# SiLPA_HE_EEM_Connectors.net
KiCad netlist of a schematic drawn in Altium Designer
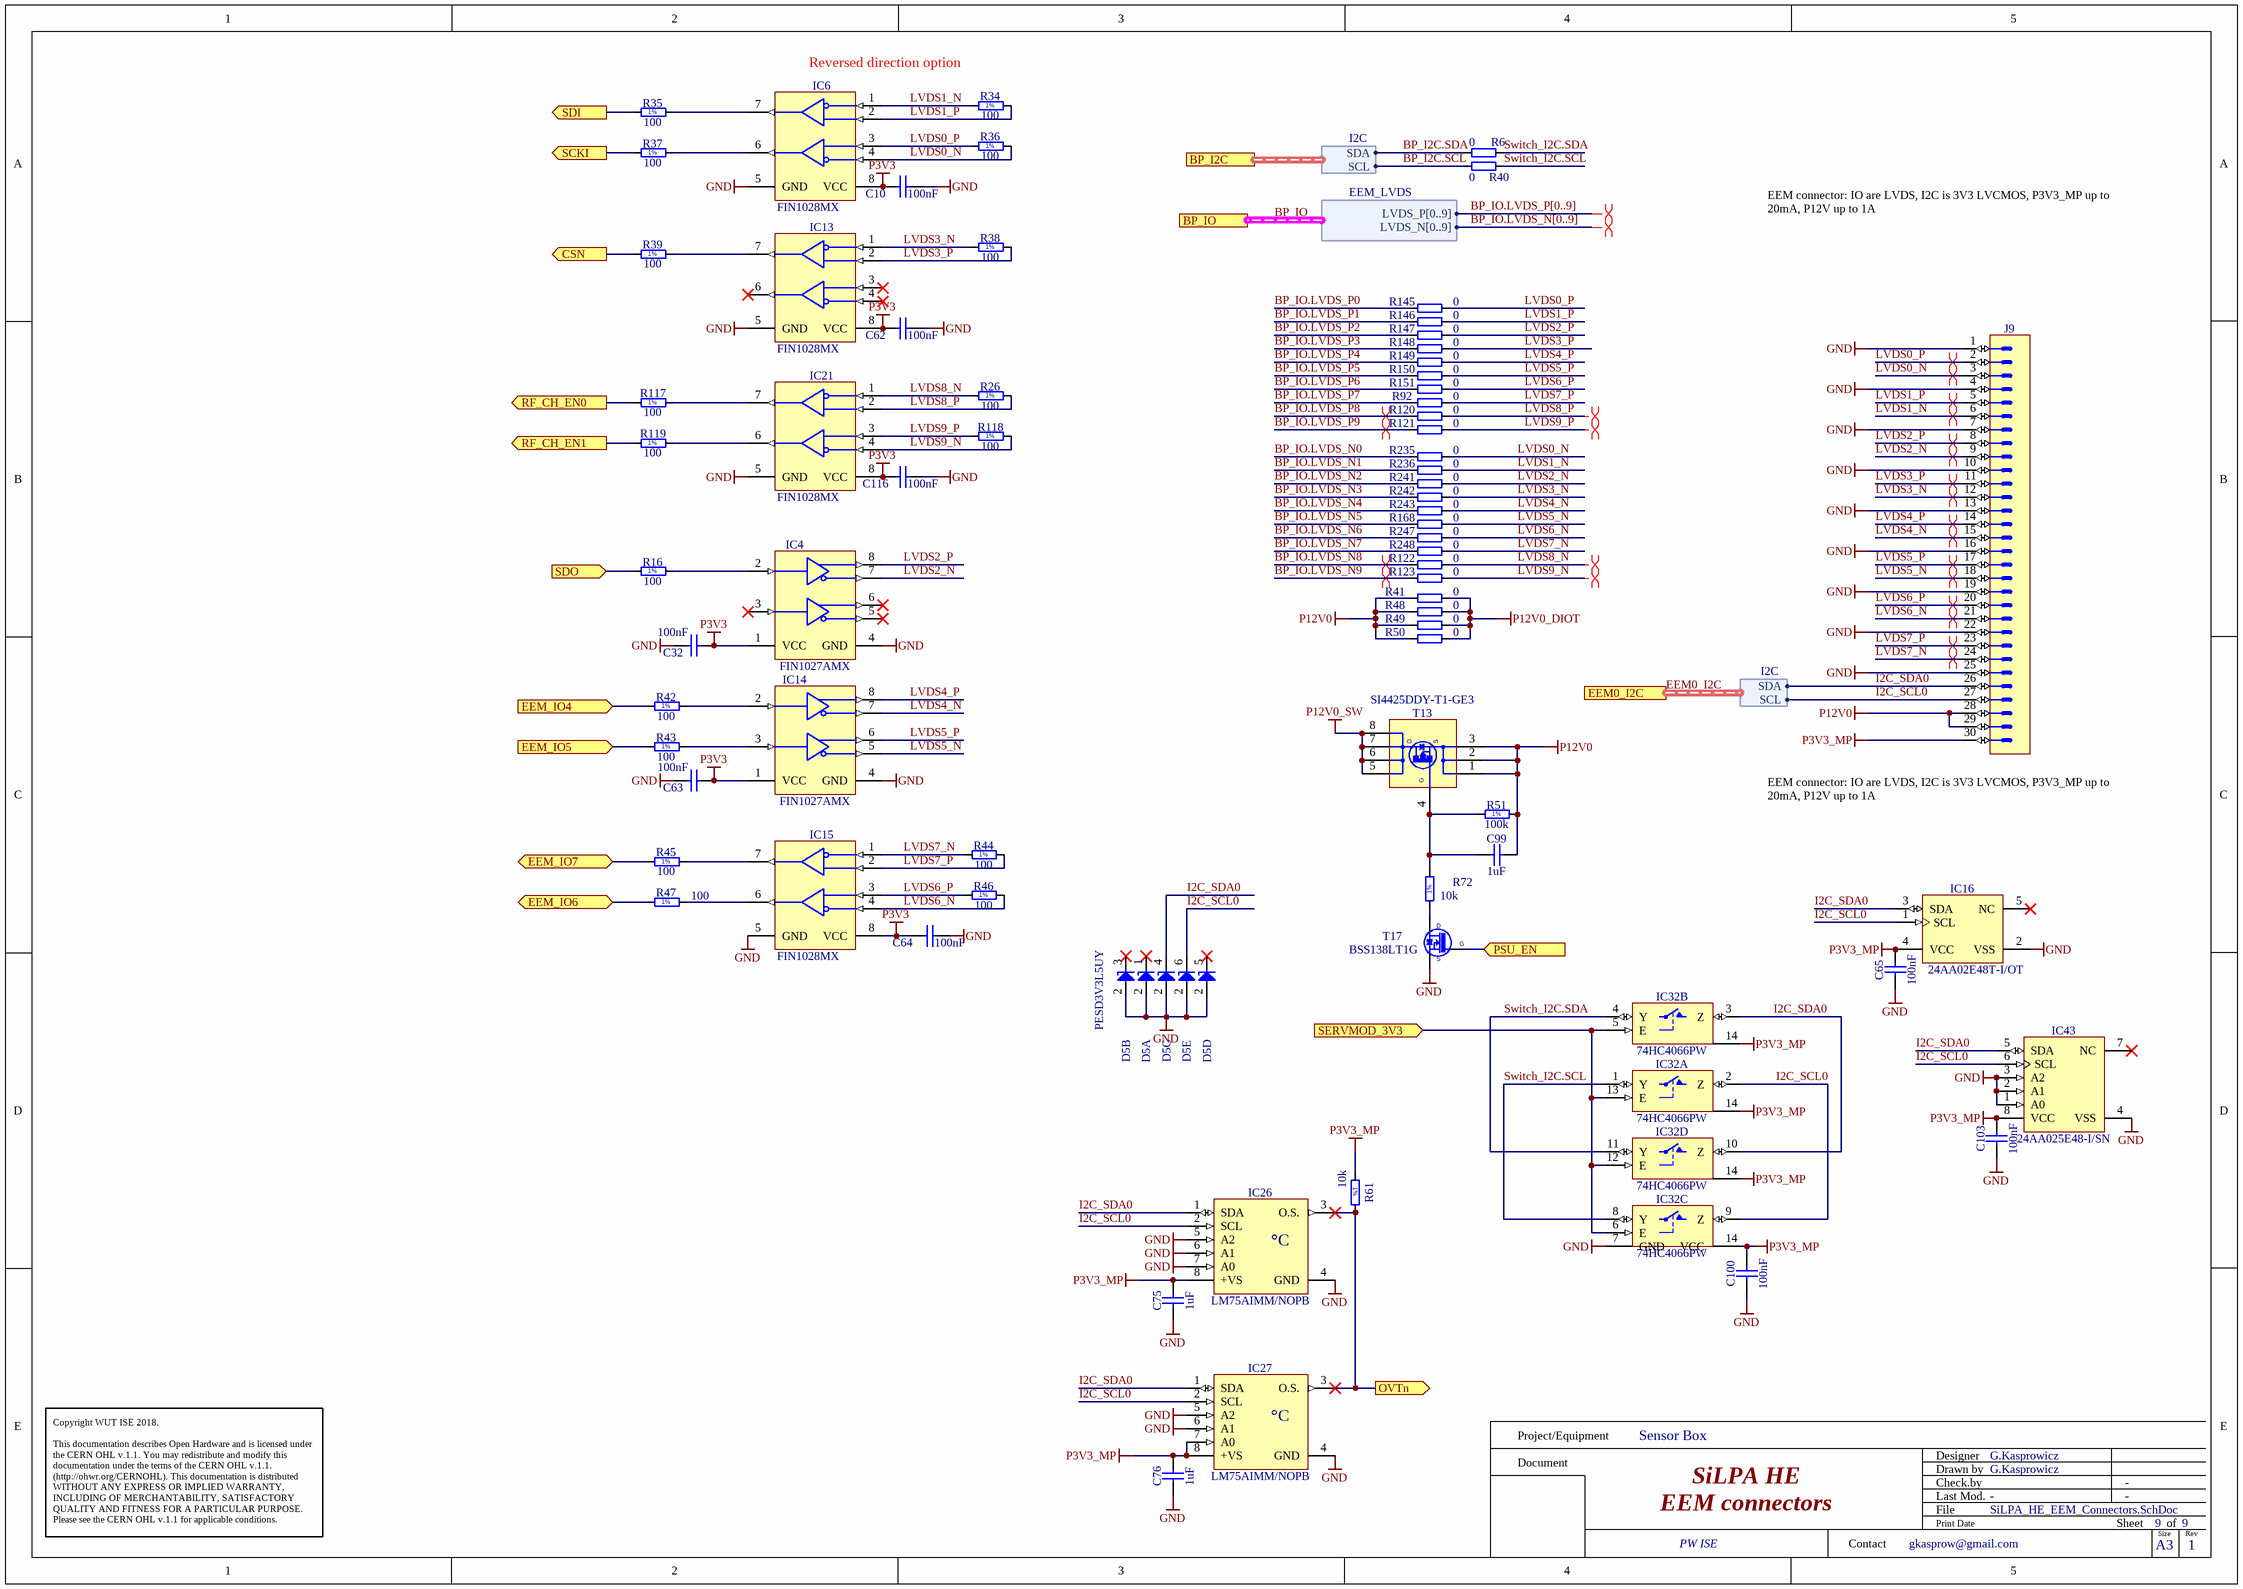
[diagram p0: SiLPA_HE_EEM_Connectors.SchDoc]

(export (version "E")
  (design (tool "Eeschema 10.0.6"))
  (components
    (comp (ref "C10")
      (value "100nF")
      (footprint "CAPC1005X55N")
      (description "Non-polarised capacitor")
      (fields
        (field (name "PART NUMBER") "CC0402_100NF_16V_10%_X5R")
        (field (name "VOLTAGE") "16V")
        (field (name "AUTHOR") "CERN DEM JLC")
      )
      (libsource (lib "Capacitors") (part "Capacitor - non polarized"))
    )
    (comp (ref "C32")
      (value "100nF")
      (footprint "CAPC1005X55N")
      (description "Non-polarised capacitor")
      (fields
        (field (name "PART NUMBER") "CC0402_100NF_16V_10%_X5R")
        (field (name "VOLTAGE") "16V")
        (field (name "AUTHOR") "CERN DEM JLC")
      )
      (libsource (lib "Capacitors") (part "Capacitor - non polarized"))
    )
    (comp (ref "C62")
      (value "100nF")
      (footprint "CAPC1005X55N")
      (description "Non-polarised capacitor")
      (fields
        (field (name "PART NUMBER") "CC0402_100NF_16V_10%_X5R")
        (field (name "VOLTAGE") "16V")
        (field (name "AUTHOR") "CERN DEM JLC")
      )
      (libsource (lib "Capacitors") (part "Capacitor - non polarized"))
    )
    (comp (ref "C63")
      (value "100nF")
      (footprint "CAPC1005X55N")
      (description "Non-polarised capacitor")
      (fields
        (field (name "PART NUMBER") "CC0402_100NF_16V_10%_X5R")
        (field (name "VOLTAGE") "16V")
        (field (name "AUTHOR") "CERN DEM JLC")
      )
      (libsource (lib "Capacitors") (part "Capacitor - non polarized"))
    )
    (comp (ref "C64")
      (value "100nF")
      (footprint "CAPC1005X55N")
      (description "Non-polarised capacitor")
      (fields
        (field (name "PART NUMBER") "CC0402_100NF_16V_10%_X5R")
        (field (name "VOLTAGE") "16V")
        (field (name "AUTHOR") "CERN DEM JLC")
      )
      (libsource (lib "Capacitors") (part "Capacitor - non polarized"))
    )
    (comp (ref "C65")
      (value "100nF")
      (footprint "CAPC1005X55N")
      (description "Non-polarised capacitor")
      (fields
        (field (name "PART NUMBER") "CC0402_100NF_16V_10%_X5R")
        (field (name "VOLTAGE") "16V")
        (field (name "AUTHOR") "CERN DEM JLC")
      )
      (libsource (lib "Capacitors") (part "Capacitor - non polarized"))
    )
    (comp (ref "C75")
      (value "1uF")
      (footprint "CAPC1005X55N")
      (description "Non-polarised capacitor")
      (fields
        (field (name "PART NUMBER") "CC0402_1UF_16V_10%_X5R")
        (field (name "VOLTAGE") "16V")
        (field (name "AUTHOR") "CERN DEM JLC")
      )
      (libsource (lib "Capacitors") (part "Capacitor - non polarized"))
    )
    (comp (ref "C76")
      (value "1uF")
      (footprint "CAPC1005X55N")
      (description "Non-polarised capacitor")
      (fields
        (field (name "PART NUMBER") "CC0402_1UF_16V_10%_X5R")
        (field (name "VOLTAGE") "16V")
        (field (name "AUTHOR") "CERN DEM JLC")
      )
      (libsource (lib "Capacitors") (part "Capacitor - non polarized"))
    )
    (comp (ref "C99")
      (value "1uF")
      (footprint "CAPC1005X55N")
      (description "Non-polarised capacitor")
      (fields
        (field (name "PART NUMBER") "CC0402_1UF_16V_10%_X5R")
        (field (name "VOLTAGE") "16V")
        (field (name "AUTHOR") "CERN DEM JLC")
      )
      (libsource (lib "Capacitors") (part "Capacitor - non polarized"))
    )
    (comp (ref "C100")
      (value "100nF")
      (footprint "CAPC1005X55N")
      (description "Non-polarised capacitor")
      (fields
        (field (name "PART NUMBER") "CC0402_100NF_16V_10%_X5R")
        (field (name "VOLTAGE") "16V")
        (field (name "AUTHOR") "CERN DEM JLC")
      )
      (libsource (lib "EEM_FMC_Carrier") (part "CC0402_100NF_16V_10%_X5R"))
    )
    (comp (ref "C103")
      (value "100nF")
      (footprint "CAPC1005X55N")
      (description "Non-polarised capacitor")
      (fields
        (field (name "PART NUMBER") "CC0402_100NF_50V_10%_X7R")
        (field (name "VOLTAGE") "50V")
        (field (name "AUTHOR") "CERN DEM MR")
      )
      (libsource (lib "Capacitors") (part "Capacitor - non polarized"))
    )
    (comp (ref "C116")
      (value "100nF")
      (footprint "CAPC1005X55N")
      (description "Non-polarised capacitor")
      (fields
        (field (name "PART NUMBER") "CC0402_100NF_16V_10%_X5R")
        (field (name "VOLTAGE") "16V")
        (field (name "AUTHOR") "CERN DEM JLC")
      )
      (libsource (lib "Capacitors") (part "Capacitor - non polarized"))
    )
    (comp (ref "D5")
      (value "PESD3V3L5UY")
      (footprint "SOT65P210X110-6N")
      (description "Fivefold ESD Protection Diode Arrays")
      (fields
        (field (name "VOLTAGE") "3.3V")
        (field (name "POWER") "200W")
        (field (name "AUTHOR") "CERN DEM WB")
      )
      (libsource (lib "EEM_FMC_Carrier") (part "PESD3V3L5UY"))
    )
    (comp (ref "IC4")
      (value "FIN1027AMX")
      (footprint "SOIC127P600X175-8N")
      (description "3.3V LVDS, 2-Bit, High-Speed, Differential Driver")
      (fields (field (name "MANUFACTURER") "ON Semiconductor") (field (name "AUTHOR") "GK"))
      (libsource (lib "LIBRARY_SCH") (part "IFC_FIN1027A"))
    )
    (comp (ref "IC6")
      (value "FIN1028MX")
      (footprint "SOIC127P600X175-8N")
      (description "3.3V LVDS 2-Bit High-Speed Differential Reciever")
      (fields (field (name "MANUFACTURER") "ON Semiconductor") (field (name "AUTHOR") "GK"))
      (libsource (lib "LIBRARY_SCH") (part "IFC_FIN1028"))
    )
    (comp (ref "IC13")
      (value "FIN1028MX")
      (footprint "SOIC127P600X175-8N")
      (description "3.3V LVDS 2-Bit High-Speed Differential Reciever")
      (fields (field (name "MANUFACTURER") "ON Semiconductor") (field (name "AUTHOR") "GK"))
      (libsource (lib "LIBRARY_SCH") (part "IFC_FIN1028"))
    )
    (comp (ref "IC14")
      (value "FIN1027AMX")
      (footprint "SOIC127P600X175-8N")
      (description "3.3V LVDS, 2-Bit, High-Speed, Differential Driver")
      (fields (field (name "MANUFACTURER") "ON Semiconductor") (field (name "AUTHOR") "GK"))
      (libsource (lib "LIBRARY_SCH") (part "IFC_FIN1027A"))
    )
    (comp (ref "IC15")
      (value "FIN1028MX")
      (footprint "SOIC127P600X175-8N")
      (description "3.3V LVDS 2-Bit High-Speed Differential Reciever")
      (fields (field (name "MANUFACTURER") "ON Semiconductor") (field (name "AUTHOR") "GK"))
      (libsource (lib "LIBRARY_SCH") (part "IFC_FIN1028"))
    )
    (comp (ref "IC16")
      (value "24AA02E48T-I/OT")
      (footprint "SOT95P280X145-5N")
      (description "1.7V-5.5V, 2K I2C Serial EEPROM With EUI-48 Node Identity")
      (fields (field (name "MANUFACTURER") "MICROCHIP TECHNOLOGY") (field (name "AUTHOR") "CERN DEM MR"))
      (libsource (lib "ICs And Semiconductors") (part "24AA02E48T-I/OT"))
    )
    (comp (ref "IC21")
      (value "FIN1028MX")
      (footprint "SOIC127P600X175-8N")
      (description "3.3V LVDS 2-Bit High-Speed Differential Reciever")
      (fields (field (name "MANUFACTURER") "ON Semiconductor") (field (name "AUTHOR") "GK"))
      (libsource (lib "LIBRARY_SCH") (part "IFC_FIN1028"))
    )
    (comp (ref "IC26")
      (value "LM75AIMM/NOPB")
      (footprint "SOP65P490X109-8N")
      (description "Digital Temperature Sensor and Thermal Watchdog with Two-Wire Interface")
      (fields (field (name "MANUFACTURER") "TEXAS INSTRUMENTS") (field (name "AUTHOR") "CERN DEM JLC"))
      (libsource (lib "ICs And Semiconductors") (part "LM75"))
    )
    (comp (ref "IC27")
      (value "LM75AIMM/NOPB")
      (footprint "SOP65P490X109-8N")
      (description "Digital Temperature Sensor and Thermal Watchdog with Two-Wire Interface")
      (fields (field (name "MANUFACTURER") "TEXAS INSTRUMENTS") (field (name "AUTHOR") "CERN DEM JLC"))
      (libsource (lib "ICs And Semiconductors") (part "LM75"))
    )
    (comp (ref "IC32")
      (value "74HC4066PW")
      (footprint "SOP65P640X110-14N")
      (fields (field (name "MANUFACTURER") "NXP SEMICONDUCTORS") (field (name "AUTHOR") "CERN DEM JLC"))
      (libsource (lib "EEM_FMC_Carrier") (part "74HC4066PW"))
    )
    (comp (ref "IC43")
      (value "24AA025E48-I/SN")
      (footprint "SOIC127P600X175-8N")
      (description "1.7V-5.5V, 2K I2C™ Serial EEPROMs with EUI-48™ Node Identity")
      (fields (field (name "MANUFACTURER") "MICROCHIP TECHNOLOGY") (field (name "AUTHOR") "CERN DEM MR"))
      (libsource (lib "ICs And Semiconductors") (part "24AA025E48-I/SN"))
    )
    (comp (ref "J9")
      (value "~")
      (footprint "3M_N2530-6002RB")
      (description "Connector 30 Male")
      (fields
        (field (name "PART NUMBER") "3M_N2530-6002RB")
        (field (name "MANUFACTURER") "3M")
        (field (name "AUTHOR") "CERN DEM JLC")
      )
      (libsource (lib "Connectors") (part "Connector 30 Male"))
    )
    (comp (ref "R6")
      (value "0")
      (footprint "RESC1005X40N")
      (description "Resistor")
      (fields
        (field (name "PART NUMBER") "R0402_0R_JUMPER")
        (field (name "MANUFACTURER") "GENERIC")
        (field (name "AUTHOR") "CERN DEM JLC")
      )
      (libsource (lib "Resistors") (part "Resistor"))
    )
    (comp (ref "R16")
      (value "100")
      (footprint "RESC1005X40N")
      (description "Resistor - 1%")
      (fields
        (field (name "PART NUMBER") "R0402_100R_1%_0.0625W_100PPM")
        (field (name "POWER") "0.0625W")
        (field (name "AUTHOR") "CERN DEM JLC")
      )
      (libsource (lib "Resistors") (part "Resistor - 1%"))
    )
    (comp (ref "R26")
      (value "100")
      (footprint "RESC1005X40N")
      (description "Resistor - 1%")
      (fields
        (field (name "PART NUMBER") "R0402_100R_1%_0.0625W_100PPM")
        (field (name "POWER") "0.0625W")
        (field (name "AUTHOR") "CERN DEM JLC")
      )
      (libsource (lib "Resistors") (part "Resistor - 1%"))
    )
    (comp (ref "R34")
      (value "100")
      (footprint "RESC1005X40N")
      (description "Resistor - 1%")
      (fields
        (field (name "PART NUMBER") "R0402_100R_1%_0.0625W_100PPM")
        (field (name "POWER") "0.0625W")
        (field (name "AUTHOR") "CERN DEM JLC")
      )
      (libsource (lib "Resistors") (part "Resistor - 1%"))
    )
    (comp (ref "R35")
      (value "100")
      (footprint "RESC1005X40N")
      (description "Resistor - 1%")
      (fields
        (field (name "PART NUMBER") "R0402_100R_1%_0.0625W_100PPM")
        (field (name "POWER") "0.0625W")
        (field (name "AUTHOR") "CERN DEM JLC")
      )
      (libsource (lib "Resistors") (part "Resistor - 1%"))
    )
    (comp (ref "R36")
      (value "100")
      (footprint "RESC1005X40N")
      (description "Resistor - 1%")
      (fields
        (field (name "PART NUMBER") "R0402_100R_1%_0.0625W_100PPM")
        (field (name "POWER") "0.0625W")
        (field (name "AUTHOR") "CERN DEM JLC")
      )
      (libsource (lib "Resistors") (part "Resistor - 1%"))
    )
    (comp (ref "R37")
      (value "100")
      (footprint "RESC1005X40N")
      (description "Resistor - 1%")
      (fields
        (field (name "PART NUMBER") "R0402_100R_1%_0.0625W_100PPM")
        (field (name "POWER") "0.0625W")
        (field (name "AUTHOR") "CERN DEM JLC")
      )
      (libsource (lib "Resistors") (part "Resistor - 1%"))
    )
    (comp (ref "R38")
      (value "100")
      (footprint "RESC1005X40N")
      (description "Resistor - 1%")
      (fields
        (field (name "PART NUMBER") "R0402_100R_1%_0.0625W_100PPM")
        (field (name "POWER") "0.0625W")
        (field (name "AUTHOR") "CERN DEM JLC")
      )
      (libsource (lib "Resistors") (part "Resistor - 1%"))
    )
    (comp (ref "R39")
      (value "100")
      (footprint "RESC1005X40N")
      (description "Resistor - 1%")
      (fields
        (field (name "PART NUMBER") "R0402_100R_1%_0.0625W_100PPM")
        (field (name "POWER") "0.0625W")
        (field (name "AUTHOR") "CERN DEM JLC")
      )
      (libsource (lib "Resistors") (part "Resistor - 1%"))
    )
    (comp (ref "R40")
      (value "0")
      (footprint "RESC1005X40N")
      (description "Resistor")
      (fields
        (field (name "PART NUMBER") "R0402_0R_JUMPER")
        (field (name "MANUFACTURER") "GENERIC")
        (field (name "AUTHOR") "CERN DEM JLC")
      )
      (libsource (lib "Resistors") (part "Resistor"))
    )
    (comp (ref "R41")
      (value "0")
      (footprint "RESC1005X40N")
      (description "Resistor")
      (fields
        (field (name "PART NUMBER") "R0402_0R_JUMPER")
        (field (name "MANUFACTURER") "GENERIC")
        (field (name "AUTHOR") "CERN DEM JLC")
      )
      (libsource (lib "Resistors") (part "Resistor"))
    )
    (comp (ref "R42")
      (value "100")
      (footprint "RESC1005X40N")
      (description "Resistor - 1%")
      (fields
        (field (name "PART NUMBER") "R0402_100R_1%_0.0625W_100PPM")
        (field (name "POWER") "0.0625W")
        (field (name "AUTHOR") "CERN DEM JLC")
      )
      (libsource (lib "Resistors") (part "Resistor - 1%"))
    )
    (comp (ref "R43")
      (value "100")
      (footprint "RESC1005X40N")
      (description "Resistor - 1%")
      (fields
        (field (name "PART NUMBER") "R0402_100R_1%_0.0625W_100PPM")
        (field (name "POWER") "0.0625W")
        (field (name "AUTHOR") "CERN DEM JLC")
      )
      (libsource (lib "Resistors") (part "Resistor - 1%"))
    )
    (comp (ref "R44")
      (value "100")
      (footprint "RESC1005X40N")
      (description "Resistor - 1%")
      (fields
        (field (name "PART NUMBER") "R0402_100R_1%_0.0625W_100PPM")
        (field (name "POWER") "0.0625W")
        (field (name "AUTHOR") "CERN DEM JLC")
      )
      (libsource (lib "Resistors") (part "Resistor - 1%"))
    )
    (comp (ref "R45")
      (value "100")
      (footprint "RESC1005X40N")
      (description "Resistor - 1%")
      (fields
        (field (name "PART NUMBER") "R0402_100R_1%_0.0625W_100PPM")
        (field (name "POWER") "0.0625W")
        (field (name "AUTHOR") "CERN DEM JLC")
      )
      (libsource (lib "Resistors") (part "Resistor - 1%"))
    )
    (comp (ref "R46")
      (value "100")
      (footprint "RESC1005X40N")
      (description "Resistor - 1%")
      (fields
        (field (name "PART NUMBER") "R0402_100R_1%_0.0625W_100PPM")
        (field (name "POWER") "0.0625W")
        (field (name "AUTHOR") "CERN DEM JLC")
      )
      (libsource (lib "Resistors") (part "Resistor - 1%"))
    )
    (comp (ref "R47")
      (value "100")
      (footprint "RESC1005X40N")
      (description "Resistor - 1%")
      (fields
        (field (name "PART NUMBER") "R0402_100R_1%_0.0625W_100PPM")
        (field (name "POWER") "0.0625W")
        (field (name "AUTHOR") "CERN DEM JLC")
      )
      (libsource (lib "Resistors") (part "Resistor - 1%"))
    )
    (comp (ref "R48")
      (value "0")
      (footprint "RESC1005X40N")
      (description "Resistor")
      (fields
        (field (name "PART NUMBER") "R0402_0R_JUMPER")
        (field (name "MANUFACTURER") "GENERIC")
        (field (name "AUTHOR") "CERN DEM JLC")
      )
      (libsource (lib "Resistors") (part "Resistor"))
    )
    (comp (ref "R49")
      (value "0")
      (footprint "RESC1005X40N")
      (description "Resistor")
      (fields
        (field (name "PART NUMBER") "R0402_0R_JUMPER")
        (field (name "MANUFACTURER") "GENERIC")
        (field (name "AUTHOR") "CERN DEM JLC")
      )
      (libsource (lib "Resistors") (part "Resistor"))
    )
    (comp (ref "R50")
      (value "0")
      (footprint "RESC1005X40N")
      (description "Resistor")
      (fields
        (field (name "PART NUMBER") "R0402_0R_JUMPER")
        (field (name "MANUFACTURER") "GENERIC")
        (field (name "AUTHOR") "CERN DEM JLC")
      )
      (libsource (lib "Resistors") (part "Resistor"))
    )
    (comp (ref "R51")
      (value "100k")
      (footprint "RESC1608X55N")
      (description "Resistor - 1%")
      (fields
        (field (name "PART NUMBER") "R0603_100K_1%_0.1W_100PPM")
        (field (name "POWER") "0.1W")
        (field (name "AUTHOR") "CERN DEM JLC")
      )
      (libsource (lib "Resistors") (part "Resistor - 1%"))
    )
    (comp (ref "R61")
      (value "10k")
      (footprint "RESC1005X40N")
      (description "Resistor - 1%")
      (fields
        (field (name "PART NUMBER") "R0402_10K_1%_0.0625W_100PPM")
        (field (name "POWER") "0.0625W")
        (field (name "AUTHOR") "CERN DEM JLC")
      )
      (libsource (lib "Resistors") (part "Resistor - 1%"))
    )
    (comp (ref "R72")
      (value "10k")
      (footprint "RESC1005X40N")
      (description "Resistor - 1%")
      (fields
        (field (name "PART NUMBER") "R0402_10K_1%_0.0625W_100PPM")
        (field (name "POWER") "0.0625W")
        (field (name "AUTHOR") "CERN DEM JLC")
      )
      (libsource (lib "Resistors") (part "Resistor - 1%"))
    )
    (comp (ref "R92")
      (value "0")
      (footprint "RESC1005X40N")
      (description "Resistor")
      (fields
        (field (name "PART NUMBER") "R0402_0R_JUMPER")
        (field (name "MANUFACTURER") "GENERIC")
        (field (name "AUTHOR") "CERN DEM JLC")
      )
      (libsource (lib "Resistors") (part "Resistor"))
    )
    (comp (ref "R117")
      (value "100")
      (footprint "RESC1005X40N")
      (description "Resistor - 1%")
      (fields
        (field (name "PART NUMBER") "R0402_100R_1%_0.0625W_100PPM")
        (field (name "POWER") "0.0625W")
        (field (name "AUTHOR") "CERN DEM JLC")
      )
      (libsource (lib "Resistors") (part "Resistor - 1%"))
    )
    (comp (ref "R118")
      (value "100")
      (footprint "RESC1005X40N")
      (description "Resistor - 1%")
      (fields
        (field (name "PART NUMBER") "R0402_100R_1%_0.0625W_100PPM")
        (field (name "POWER") "0.0625W")
        (field (name "AUTHOR") "CERN DEM JLC")
      )
      (libsource (lib "Resistors") (part "Resistor - 1%"))
    )
    (comp (ref "R119")
      (value "100")
      (footprint "RESC1005X40N")
      (description "Resistor - 1%")
      (fields
        (field (name "PART NUMBER") "R0402_100R_1%_0.0625W_100PPM")
        (field (name "POWER") "0.0625W")
        (field (name "AUTHOR") "CERN DEM JLC")
      )
      (libsource (lib "Resistors") (part "Resistor - 1%"))
    )
    (comp (ref "R120")
      (value "0")
      (footprint "RESC1005X40N")
      (description "Resistor")
      (fields
        (field (name "PART NUMBER") "R0402_0R_JUMPER")
        (field (name "MANUFACTURER") "GENERIC")
        (field (name "AUTHOR") "CERN DEM JLC")
      )
      (libsource (lib "Resistors") (part "Resistor"))
    )
    (comp (ref "R121")
      (value "0")
      (footprint "RESC1005X40N")
      (description "Resistor")
      (fields
        (field (name "PART NUMBER") "R0402_0R_JUMPER")
        (field (name "MANUFACTURER") "GENERIC")
        (field (name "AUTHOR") "CERN DEM JLC")
      )
      (libsource (lib "Resistors") (part "Resistor"))
    )
    (comp (ref "R122")
      (value "0")
      (footprint "RESC1005X40N")
      (description "Resistor")
      (fields
        (field (name "PART NUMBER") "R0402_0R_JUMPER")
        (field (name "MANUFACTURER") "GENERIC")
        (field (name "AUTHOR") "CERN DEM JLC")
      )
      (libsource (lib "Resistors") (part "Resistor"))
    )
    (comp (ref "R123")
      (value "0")
      (footprint "RESC1005X40N")
      (description "Resistor")
      (fields
        (field (name "PART NUMBER") "R0402_0R_JUMPER")
        (field (name "MANUFACTURER") "GENERIC")
        (field (name "AUTHOR") "CERN DEM JLC")
      )
      (libsource (lib "Resistors") (part "Resistor"))
    )
    (comp (ref "R145")
      (value "0")
      (footprint "RESC1005X40N")
      (description "Resistor")
      (fields
        (field (name "PART NUMBER") "R0402_0R_JUMPER")
        (field (name "MANUFACTURER") "GENERIC")
        (field (name "AUTHOR") "CERN DEM JLC")
      )
      (libsource (lib "Resistors") (part "Resistor"))
    )
    (comp (ref "R146")
      (value "0")
      (footprint "RESC1005X40N")
      (description "Resistor")
      (fields
        (field (name "PART NUMBER") "R0402_0R_JUMPER")
        (field (name "MANUFACTURER") "GENERIC")
        (field (name "AUTHOR") "CERN DEM JLC")
      )
      (libsource (lib "Resistors") (part "Resistor"))
    )
    (comp (ref "R147")
      (value "0")
      (footprint "RESC1005X40N")
      (description "Resistor")
      (fields
        (field (name "PART NUMBER") "R0402_0R_JUMPER")
        (field (name "MANUFACTURER") "GENERIC")
        (field (name "AUTHOR") "CERN DEM JLC")
      )
      (libsource (lib "Resistors") (part "Resistor"))
    )
    (comp (ref "R148")
      (value "0")
      (footprint "RESC1005X40N")
      (description "Resistor")
      (fields
        (field (name "PART NUMBER") "R0402_0R_JUMPER")
        (field (name "MANUFACTURER") "GENERIC")
        (field (name "AUTHOR") "CERN DEM JLC")
      )
      (libsource (lib "Resistors") (part "Resistor"))
    )
    (comp (ref "R149")
      (value "0")
      (footprint "RESC1005X40N")
      (description "Resistor")
      (fields
        (field (name "PART NUMBER") "R0402_0R_JUMPER")
        (field (name "MANUFACTURER") "GENERIC")
        (field (name "AUTHOR") "CERN DEM JLC")
      )
      (libsource (lib "Resistors") (part "Resistor"))
    )
    (comp (ref "R150")
      (value "0")
      (footprint "RESC1005X40N")
      (description "Resistor")
      (fields
        (field (name "PART NUMBER") "R0402_0R_JUMPER")
        (field (name "MANUFACTURER") "GENERIC")
        (field (name "AUTHOR") "CERN DEM JLC")
      )
      (libsource (lib "Resistors") (part "Resistor"))
    )
    (comp (ref "R151")
      (value "0")
      (footprint "RESC1005X40N")
      (description "Resistor")
      (fields
        (field (name "PART NUMBER") "R0402_0R_JUMPER")
        (field (name "MANUFACTURER") "GENERIC")
        (field (name "AUTHOR") "CERN DEM JLC")
      )
      (libsource (lib "Resistors") (part "Resistor"))
    )
    (comp (ref "R168")
      (value "0")
      (footprint "RESC1005X40N")
      (description "Resistor")
      (fields
        (field (name "PART NUMBER") "R0402_0R_JUMPER")
        (field (name "MANUFACTURER") "GENERIC")
        (field (name "AUTHOR") "CERN DEM JLC")
      )
      (libsource (lib "Resistors") (part "Resistor"))
    )
    (comp (ref "R235")
      (value "0")
      (footprint "RESC1005X40N")
      (description "Resistor")
      (fields
        (field (name "PART NUMBER") "R0402_0R_JUMPER")
        (field (name "MANUFACTURER") "GENERIC")
        (field (name "AUTHOR") "CERN DEM JLC")
      )
      (libsource (lib "Resistors") (part "Resistor"))
    )
    (comp (ref "R236")
      (value "0")
      (footprint "RESC1005X40N")
      (description "Resistor")
      (fields
        (field (name "PART NUMBER") "R0402_0R_JUMPER")
        (field (name "MANUFACTURER") "GENERIC")
        (field (name "AUTHOR") "CERN DEM JLC")
      )
      (libsource (lib "Resistors") (part "Resistor"))
    )
    (comp (ref "R241")
      (value "0")
      (footprint "RESC1005X40N")
      (description "Resistor")
      (fields
        (field (name "PART NUMBER") "R0402_0R_JUMPER")
        (field (name "MANUFACTURER") "GENERIC")
        (field (name "AUTHOR") "CERN DEM JLC")
      )
      (libsource (lib "Resistors") (part "Resistor"))
    )
    (comp (ref "R242")
      (value "0")
      (footprint "RESC1005X40N")
      (description "Resistor")
      (fields
        (field (name "PART NUMBER") "R0402_0R_JUMPER")
        (field (name "MANUFACTURER") "GENERIC")
        (field (name "AUTHOR") "CERN DEM JLC")
      )
      (libsource (lib "Resistors") (part "Resistor"))
    )
    (comp (ref "R243")
      (value "0")
      (footprint "RESC1005X40N")
      (description "Resistor")
      (fields
        (field (name "PART NUMBER") "R0402_0R_JUMPER")
        (field (name "MANUFACTURER") "GENERIC")
        (field (name "AUTHOR") "CERN DEM JLC")
      )
      (libsource (lib "Resistors") (part "Resistor"))
    )
    (comp (ref "R247")
      (value "0")
      (footprint "RESC1005X40N")
      (description "Resistor")
      (fields
        (field (name "PART NUMBER") "R0402_0R_JUMPER")
        (field (name "MANUFACTURER") "GENERIC")
        (field (name "AUTHOR") "CERN DEM JLC")
      )
      (libsource (lib "Resistors") (part "Resistor"))
    )
    (comp (ref "R248")
      (value "0")
      (footprint "RESC1005X40N")
      (description "Resistor")
      (fields
        (field (name "PART NUMBER") "R0402_0R_JUMPER")
        (field (name "MANUFACTURER") "GENERIC")
        (field (name "AUTHOR") "CERN DEM JLC")
      )
      (libsource (lib "Resistors") (part "Resistor"))
    )
    (comp (ref "T13")
      (value "SI4425DDY-T1-GE3")
      (footprint "SOIC127P600X175-8N")
      (description "-30V -19.7A P-Channel MOSFET")
      (fields (field (name "MANUFACTURER") "VISHAY SILICONIX") (field (name "AUTHOR") "CERN DEM MR"))
      (libsource (lib "ICs And Semiconductors") (part "SI4425DDY"))
    )
    (comp (ref "T17")
      (value "BSS138LT1G")
      (footprint "SOT95P240X110-3N")
      (description "N-CHANNEL MOSFET WITH DIODE")
      (fields (field (name "MANUFACTURER") "ON SEMICONDUCTOR") (field (name "AUTHOR") "CERN DEM JLC"))
      (libsource (lib "ICs And Semiconductors") (part "N-MOSFET-D 1G 2S 3D"))
    )
  )
  (nets
    (net (code "4") (name "/BP_I2C.SCL") (class "Default")
      (node (ref "R40") (pin "1") (pinfunction "1_1") (pintype "passive"))
    )
    (net (code "5") (name "/BP_I2C.SDA") (class "Default")
      (node (ref "R6") (pin "1") (pinfunction "1_1") (pintype "passive"))
    )
    (net (code "6") (name "/BP_IO.LVDS_N0") (class "Default")
      (node (ref "R235") (pin "1") (pinfunction "1_1") (pintype "passive"))
    )
    (net (code "7") (name "/BP_IO.LVDS_N1") (class "Default")
      (node (ref "R236") (pin "1") (pinfunction "1_1") (pintype "passive"))
    )
    (net (code "8") (name "/BP_IO.LVDS_N2") (class "Default")
      (node (ref "R241") (pin "1") (pinfunction "1_1") (pintype "passive"))
    )
    (net (code "9") (name "/BP_IO.LVDS_N3") (class "Default")
      (node (ref "R242") (pin "1") (pinfunction "1_1") (pintype "passive"))
    )
    (net (code "10") (name "/BP_IO.LVDS_N4") (class "Default")
      (node (ref "R243") (pin "1") (pinfunction "1_1") (pintype "passive"))
    )
    (net (code "11") (name "/BP_IO.LVDS_N5") (class "Default")
      (node (ref "R168") (pin "1") (pinfunction "1_1") (pintype "passive"))
    )
    (net (code "12") (name "/BP_IO.LVDS_N6") (class "Default")
      (node (ref "R247") (pin "1") (pinfunction "1_1") (pintype "passive"))
    )
    (net (code "13") (name "/BP_IO.LVDS_N7") (class "Default")
      (node (ref "R248") (pin "1") (pinfunction "1_1") (pintype "passive"))
    )
    (net (code "14") (name "/BP_IO.LVDS_N8") (class "Default")
      (node (ref "R122") (pin "1") (pinfunction "1_1") (pintype "passive"))
    )
    (net (code "15") (name "/BP_IO.LVDS_N9") (class "Default")
      (node (ref "R123") (pin "1") (pinfunction "1_1") (pintype "passive"))
    )
    (net (code "17") (name "/BP_IO.LVDS_P0") (class "Default")
      (node (ref "R145") (pin "1") (pinfunction "1_1") (pintype "passive"))
    )
    (net (code "18") (name "/BP_IO.LVDS_P1") (class "Default")
      (node (ref "R146") (pin "1") (pinfunction "1_1") (pintype "passive"))
    )
    (net (code "19") (name "/BP_IO.LVDS_P2") (class "Default")
      (node (ref "R147") (pin "1") (pinfunction "1_1") (pintype "passive"))
    )
    (net (code "20") (name "/BP_IO.LVDS_P3") (class "Default")
      (node (ref "R148") (pin "1") (pinfunction "1_1") (pintype "passive"))
    )
    (net (code "21") (name "/BP_IO.LVDS_P4") (class "Default")
      (node (ref "R149") (pin "1") (pinfunction "1_1") (pintype "passive"))
    )
    (net (code "22") (name "/BP_IO.LVDS_P5") (class "Default")
      (node (ref "R150") (pin "1") (pinfunction "1_1") (pintype "passive"))
    )
    (net (code "23") (name "/BP_IO.LVDS_P6") (class "Default")
      (node (ref "R151") (pin "1") (pinfunction "1_1") (pintype "passive"))
    )
    (net (code "24") (name "/BP_IO.LVDS_P7") (class "Default")
      (node (ref "R92") (pin "1") (pinfunction "1_1") (pintype "passive"))
    )
    (net (code "25") (name "/BP_IO.LVDS_P8") (class "Default")
      (node (ref "R120") (pin "1") (pinfunction "1_1") (pintype "passive"))
    )
    (net (code "26") (name "/BP_IO.LVDS_P9") (class "Default")
      (node (ref "R121") (pin "1") (pinfunction "1_1") (pintype "passive"))
    )
    (net (code "27") (name "/CSN") (class "Default")
      (node (ref "R39") (pin "1") (pinfunction "1_1") (pintype "passive"))
    )
    (net (code "29") (name "/EEM_IO4") (class "Default")
      (node (ref "R42") (pin "1") (pinfunction "1_1") (pintype "passive"))
    )
    (net (code "30") (name "/EEM_IO5") (class "Default")
      (node (ref "R43") (pin "1") (pinfunction "1_1") (pintype "passive"))
    )
    (net (code "31") (name "/EEM_IO6") (class "Default")
      (node (ref "R47") (pin "1") (pinfunction "1_1") (pintype "passive"))
    )
    (net (code "32") (name "/EEM_IO7") (class "Default")
      (node (ref "R45") (pin "1") (pinfunction "1_1") (pintype "passive"))
    )
    (net (code "33") (name "/I2C_SCL0") (class "Default")
      (node (ref "D5") (pin "6") (pinfunction "C_6") (pintype "passive"))
      (node (ref "IC16") (pin "1") (pinfunction "SCL_1") (pintype "input"))
      (node (ref "IC26") (pin "2") (pinfunction "SCL_2") (pintype "input"))
      (node (ref "IC27") (pin "2") (pinfunction "SCL_2") (pintype "input"))
      (node (ref "IC32") (pin "2") (pinfunction "Z_2") (pintype "bidirectional"))
      (node (ref "IC32") (pin "9") (pinfunction "Z_9") (pintype "bidirectional"))
      (node (ref "IC43") (pin "6") (pinfunction "SCL_6") (pintype "input"))
      (node (ref "J9") (pin "27") (pinfunction "27_27") (pintype "bidirectional"))
    )
    (net (code "34") (name "/I2C_SDA0") (class "Default")
      (node (ref "D5") (pin "4") (pinfunction "C_4") (pintype "passive"))
      (node (ref "IC16") (pin "3") (pinfunction "SDA_3") (pintype "bidirectional"))
      (node (ref "IC26") (pin "1") (pinfunction "SDA_1") (pintype "bidirectional"))
      (node (ref "IC27") (pin "1") (pinfunction "SDA_1") (pintype "bidirectional"))
      (node (ref "IC32") (pin "10") (pinfunction "Z_10") (pintype "bidirectional"))
      (node (ref "IC32") (pin "3") (pinfunction "Z_3") (pintype "bidirectional"))
      (node (ref "IC43") (pin "5") (pinfunction "SDA_5") (pintype "bidirectional"))
      (node (ref "J9") (pin "26") (pinfunction "26_26") (pintype "bidirectional"))
    )
    (net (code "35") (name "/LVDS0_N") (class "Default")
      (node (ref "IC6") (pin "4") (pinfunction "RIN2-_4") (pintype "input"))
      (node (ref "J9") (pin "3") (pinfunction "3_3") (pintype "bidirectional"))
      (node (ref "R235") (pin "2") (pinfunction "2_2") (pintype "passive"))
      (node (ref "R36") (pin "2") (pinfunction "2_2") (pintype "passive"))
    )
    (net (code "36") (name "/LVDS0_P") (class "Default")
      (node (ref "IC6") (pin "3") (pinfunction "RIN2+_3") (pintype "input"))
      (node (ref "J9") (pin "2") (pinfunction "2_2") (pintype "bidirectional"))
      (node (ref "R145") (pin "2") (pinfunction "2_2") (pintype "passive"))
      (node (ref "R36") (pin "1") (pinfunction "1_1") (pintype "passive"))
    )
    (net (code "37") (name "/LVDS1_N") (class "Default")
      (node (ref "IC6") (pin "1") (pinfunction "RIN1-_1") (pintype "input"))
      (node (ref "J9") (pin "6") (pinfunction "6_6") (pintype "bidirectional"))
      (node (ref "R236") (pin "2") (pinfunction "2_2") (pintype "passive"))
      (node (ref "R34") (pin "1") (pinfunction "1_1") (pintype "passive"))
    )
    (net (code "38") (name "/LVDS1_P") (class "Default")
      (node (ref "IC6") (pin "2") (pinfunction "RIN1+_2") (pintype "input"))
      (node (ref "J9") (pin "5") (pinfunction "5_5") (pintype "bidirectional"))
      (node (ref "R146") (pin "2") (pinfunction "2_2") (pintype "passive"))
      (node (ref "R34") (pin "2") (pinfunction "2_2") (pintype "passive"))
    )
    (net (code "39") (name "/LVDS2_N") (class "Default")
      (node (ref "IC4") (pin "7") (pinfunction "DOUT-_7") (pintype "output"))
      (node (ref "J9") (pin "9") (pinfunction "9_9") (pintype "bidirectional"))
      (node (ref "R241") (pin "2") (pinfunction "2_2") (pintype "passive"))
    )
    (net (code "40") (name "/LVDS2_P") (class "Default")
      (node (ref "IC4") (pin "8") (pinfunction "DOUT+_8") (pintype "output"))
      (node (ref "J9") (pin "8") (pinfunction "8_8") (pintype "bidirectional"))
      (node (ref "R147") (pin "2") (pinfunction "2_2") (pintype "passive"))
    )
    (net (code "41") (name "/LVDS3_N") (class "Default")
      (node (ref "IC13") (pin "1") (pinfunction "RIN1-_1") (pintype "input"))
      (node (ref "J9") (pin "12") (pinfunction "12_12") (pintype "bidirectional"))
      (node (ref "R242") (pin "2") (pinfunction "2_2") (pintype "passive"))
      (node (ref "R38") (pin "1") (pinfunction "1_1") (pintype "passive"))
    )
    (net (code "42") (name "/LVDS3_P") (class "Default")
      (node (ref "IC13") (pin "2") (pinfunction "RIN1+_2") (pintype "input"))
      (node (ref "J9") (pin "11") (pinfunction "11_11") (pintype "bidirectional"))
      (node (ref "R148") (pin "2") (pinfunction "2_2") (pintype "passive"))
      (node (ref "R38") (pin "2") (pinfunction "2_2") (pintype "passive"))
    )
    (net (code "43") (name "/LVDS4_N") (class "Default")
      (node (ref "IC14") (pin "7") (pinfunction "DOUT-_7") (pintype "output"))
      (node (ref "J9") (pin "15") (pinfunction "15_15") (pintype "bidirectional"))
      (node (ref "R243") (pin "2") (pinfunction "2_2") (pintype "passive"))
    )
    (net (code "44") (name "/LVDS4_P") (class "Default")
      (node (ref "IC14") (pin "8") (pinfunction "DOUT+_8") (pintype "output"))
      (node (ref "J9") (pin "14") (pinfunction "14_14") (pintype "bidirectional"))
      (node (ref "R149") (pin "2") (pinfunction "2_2") (pintype "passive"))
    )
    (net (code "45") (name "/LVDS5_N") (class "Default")
      (node (ref "IC14") (pin "5") (pinfunction "DOUT-_5") (pintype "output"))
      (node (ref "J9") (pin "18") (pinfunction "18_18") (pintype "bidirectional"))
      (node (ref "R168") (pin "2") (pinfunction "2_2") (pintype "passive"))
    )
    (net (code "46") (name "/LVDS5_P") (class "Default")
      (node (ref "IC14") (pin "6") (pinfunction "DOUT+_6") (pintype "output"))
      (node (ref "J9") (pin "17") (pinfunction "17_17") (pintype "bidirectional"))
      (node (ref "R150") (pin "2") (pinfunction "2_2") (pintype "passive"))
    )
    (net (code "47") (name "/LVDS6_N") (class "Default")
      (node (ref "IC15") (pin "4") (pinfunction "RIN2-_4") (pintype "input"))
      (node (ref "J9") (pin "21") (pinfunction "21_21") (pintype "bidirectional"))
      (node (ref "R247") (pin "2") (pinfunction "2_2") (pintype "passive"))
      (node (ref "R46") (pin "2") (pinfunction "2_2") (pintype "passive"))
    )
    (net (code "48") (name "/LVDS6_P") (class "Default")
      (node (ref "IC15") (pin "3") (pinfunction "RIN2+_3") (pintype "input"))
      (node (ref "J9") (pin "20") (pinfunction "20_20") (pintype "bidirectional"))
      (node (ref "R151") (pin "2") (pinfunction "2_2") (pintype "passive"))
      (node (ref "R46") (pin "1") (pinfunction "1_1") (pintype "passive"))
    )
    (net (code "49") (name "/LVDS7_N") (class "Default")
      (node (ref "IC15") (pin "1") (pinfunction "RIN1-_1") (pintype "input"))
      (node (ref "J9") (pin "24") (pinfunction "24_24") (pintype "bidirectional"))
      (node (ref "R248") (pin "2") (pinfunction "2_2") (pintype "passive"))
      (node (ref "R44") (pin "1") (pinfunction "1_1") (pintype "passive"))
    )
    (net (code "50") (name "/LVDS7_P") (class "Default")
      (node (ref "IC15") (pin "2") (pinfunction "RIN1+_2") (pintype "input"))
      (node (ref "J9") (pin "23") (pinfunction "23_23") (pintype "bidirectional"))
      (node (ref "R44") (pin "2") (pinfunction "2_2") (pintype "passive"))
      (node (ref "R92") (pin "2") (pinfunction "2_2") (pintype "passive"))
    )
    (net (code "51") (name "/LVDS8_N") (class "Default")
      (node (ref "IC21") (pin "1") (pinfunction "RIN1-_1") (pintype "input"))
      (node (ref "R122") (pin "2") (pinfunction "2_2") (pintype "passive"))
      (node (ref "R26") (pin "1") (pinfunction "1_1") (pintype "passive"))
    )
    (net (code "52") (name "/LVDS8_P") (class "Default")
      (node (ref "IC21") (pin "2") (pinfunction "RIN1+_2") (pintype "input"))
      (node (ref "R120") (pin "2") (pinfunction "2_2") (pintype "passive"))
      (node (ref "R26") (pin "2") (pinfunction "2_2") (pintype "passive"))
    )
    (net (code "53") (name "/LVDS9_N") (class "Default")
      (node (ref "IC21") (pin "4") (pinfunction "RIN2-_4") (pintype "input"))
      (node (ref "R118") (pin "2") (pinfunction "2_2") (pintype "passive"))
      (node (ref "R123") (pin "2") (pinfunction "2_2") (pintype "passive"))
    )
    (net (code "54") (name "/LVDS9_P") (class "Default")
      (node (ref "IC21") (pin "3") (pinfunction "RIN2+_3") (pintype "input"))
      (node (ref "R118") (pin "1") (pinfunction "1_1") (pintype "passive"))
      (node (ref "R121") (pin "2") (pinfunction "2_2") (pintype "passive"))
    )
    (net (code "55") (name "/OVTn") (class "Default")
      (node (ref "IC26") (pin "3") (pinfunction "O.S._3") (pintype "output"))
      (node (ref "IC27") (pin "3") (pinfunction "O.S._3") (pintype "output"))
      (node (ref "R61") (pin "2") (pinfunction "2_2") (pintype "passive"))
    )
    (net (code "56") (name "/PSU_EN") (class "Default")
      (node (ref "T17") (pin "1") (pinfunction "G_1") (pintype "passive"))
    )
    (net (code "57") (name "/RF_CH_EN0") (class "Default")
      (node (ref "R117") (pin "1") (pinfunction "1_1") (pintype "passive"))
    )
    (net (code "58") (name "/RF_CH_EN1") (class "Default")
      (node (ref "R119") (pin "1") (pinfunction "1_1") (pintype "passive"))
    )
    (net (code "59") (name "/SCKI") (class "Default")
      (node (ref "R37") (pin "1") (pinfunction "1_1") (pintype "passive"))
    )
    (net (code "60") (name "/SDI") (class "Default")
      (node (ref "R35") (pin "1") (pinfunction "1_1") (pintype "passive"))
    )
    (net (code "61") (name "/SDO") (class "Default")
      (node (ref "R16") (pin "1") (pinfunction "1_1") (pintype "passive"))
    )
    (net (code "62") (name "/SERVMOD_3V3") (class "Default")
      (node (ref "IC32") (pin "12") (pinfunction "E_12") (pintype "input"))
      (node (ref "IC32") (pin "13") (pinfunction "E_13") (pintype "input"))
      (node (ref "IC32") (pin "5") (pinfunction "E_5") (pintype "input"))
      (node (ref "IC32") (pin "6") (pinfunction "E_6") (pintype "input"))
    )
    (net (code "63") (name "/Switch_I2C.SCL") (class "Default")
      (node (ref "IC32") (pin "1") (pinfunction "Y_1") (pintype "bidirectional"))
      (node (ref "IC32") (pin "8") (pinfunction "Y_8") (pintype "bidirectional"))
      (node (ref "R40") (pin "2") (pinfunction "2_2") (pintype "passive"))
    )
    (net (code "64") (name "/Switch_I2C.SDA") (class "Default")
      (node (ref "IC32") (pin "11") (pinfunction "Y_11") (pintype "bidirectional"))
      (node (ref "IC32") (pin "4") (pinfunction "Y_4") (pintype "bidirectional"))
      (node (ref "R6") (pin "2") (pinfunction "2_2") (pintype "passive"))
    )
    (net (code "68") (name "GND") (class "Default")
      (node (ref "C10") (pin "1") (pinfunction "1_1") (pintype "passive"))
      (node (ref "C100") (pin "1") (pinfunction "1_1") (pintype "passive"))
      (node (ref "C103") (pin "1") (pinfunction "1_1") (pintype "passive"))
      (node (ref "C116") (pin "1") (pinfunction "1_1") (pintype "passive"))
      (node (ref "C32") (pin "1") (pinfunction "1_1") (pintype "passive"))
      (node (ref "C62") (pin "1") (pinfunction "1_1") (pintype "passive"))
      (node (ref "C63") (pin "1") (pinfunction "1_1") (pintype "passive"))
      (node (ref "C64") (pin "1") (pinfunction "1_1") (pintype "passive"))
      (node (ref "C65") (pin "1") (pinfunction "1_1") (pintype "passive"))
      (node (ref "C75") (pin "1") (pinfunction "1_1") (pintype "passive"))
      (node (ref "C76") (pin "1") (pinfunction "1_1") (pintype "passive"))
      (node (ref "D5") (pin "2") (pinfunction "A_2") (pintype "passive"))
      (node (ref "IC13") (pin "5") (pinfunction "GND_5") (pintype "power_in"))
      (node (ref "IC14") (pin "4") (pinfunction "GND_4") (pintype "power_in"))
      (node (ref "IC15") (pin "5") (pinfunction "GND_5") (pintype "power_in"))
      (node (ref "IC16") (pin "2") (pinfunction "VSS_2") (pintype "power_in"))
      (node (ref "IC21") (pin "5") (pinfunction "GND_5") (pintype "power_in"))
      (node (ref "IC26") (pin "4") (pinfunction "GND_4") (pintype "power_in"))
      (node (ref "IC26") (pin "5") (pinfunction "A2_5") (pintype "input"))
      (node (ref "IC26") (pin "6") (pinfunction "A1_6") (pintype "input"))
      (node (ref "IC26") (pin "7") (pinfunction "A0_7") (pintype "input"))
      (node (ref "IC27") (pin "4") (pinfunction "GND_4") (pintype "power_in"))
      (node (ref "IC27") (pin "5") (pinfunction "A2_5") (pintype "input"))
      (node (ref "IC27") (pin "6") (pinfunction "A1_6") (pintype "input"))
      (node (ref "IC32") (pin "7") (pinfunction "GND_7") (pintype "power_in"))
      (node (ref "IC4") (pin "4") (pinfunction "GND_4") (pintype "power_in"))
      (node (ref "IC43") (pin "1") (pinfunction "A0_1") (pintype "input"))
      (node (ref "IC43") (pin "2") (pinfunction "A1_2") (pintype "input"))
      (node (ref "IC43") (pin "3") (pinfunction "A2_3") (pintype "input"))
      (node (ref "IC43") (pin "4") (pinfunction "VSS_4") (pintype "power_in"))
      (node (ref "IC6") (pin "5") (pinfunction "GND_5") (pintype "power_in"))
      (node (ref "J9") (pin "1") (pinfunction "1_1") (pintype "bidirectional"))
      (node (ref "J9") (pin "10") (pinfunction "10_10") (pintype "bidirectional"))
      (node (ref "J9") (pin "13") (pinfunction "13_13") (pintype "bidirectional"))
      (node (ref "J9") (pin "16") (pinfunction "16_16") (pintype "bidirectional"))
      (node (ref "J9") (pin "19") (pinfunction "19_19") (pintype "bidirectional"))
      (node (ref "J9") (pin "22") (pinfunction "22_22") (pintype "bidirectional"))
      (node (ref "J9") (pin "25") (pinfunction "25_25") (pintype "bidirectional"))
      (node (ref "J9") (pin "4") (pinfunction "4_4") (pintype "bidirectional"))
      (node (ref "J9") (pin "7") (pinfunction "7_7") (pintype "bidirectional"))
      (node (ref "T17") (pin "2") (pinfunction "S_2") (pintype "passive"))
    )
    (net (code "69") (name "Net-(C99-Pad1)") (class "Default")
      (node (ref "C99") (pin "1") (pinfunction "1_1") (pintype "passive"))
      (node (ref "R51") (pin "1") (pinfunction "1_1") (pintype "passive"))
      (node (ref "R72") (pin "2") (pinfunction "2_2") (pintype "passive"))
      (node (ref "T13") (pin "4") (pinfunction "S_4") (pintype "passive"))
    )
    (net (code "70") (name "Net-(IC4-DIN1)") (class "Default")
      (node (ref "IC4") (pin "2") (pinfunction "DIN1_2") (pintype "input"))
      (node (ref "R16") (pin "2") (pinfunction "2_2") (pintype "passive"))
    )
    (net (code "71") (name "Net-(IC6-ROUT1)") (class "Default")
      (node (ref "IC6") (pin "7") (pinfunction "ROUT1_7") (pintype "output"))
      (node (ref "R35") (pin "2") (pinfunction "2_2") (pintype "passive"))
    )
    (net (code "72") (name "Net-(IC6-ROUT2)") (class "Default")
      (node (ref "IC6") (pin "6") (pinfunction "ROUT2_6") (pintype "output"))
      (node (ref "R37") (pin "2") (pinfunction "2_2") (pintype "passive"))
    )
    (net (code "73") (name "Net-(IC13-ROUT1)") (class "Default")
      (node (ref "IC13") (pin "7") (pinfunction "ROUT1_7") (pintype "output"))
      (node (ref "R39") (pin "2") (pinfunction "2_2") (pintype "passive"))
    )
    (net (code "74") (name "Net-(IC14-DIN1)") (class "Default")
      (node (ref "IC14") (pin "2") (pinfunction "DIN1_2") (pintype "input"))
      (node (ref "R42") (pin "2") (pinfunction "2_2") (pintype "passive"))
    )
    (net (code "75") (name "Net-(IC14-DIN2RIN-)") (class "Default")
      (node (ref "IC14") (pin "3") (pinfunction "DIN2RIN-_3") (pintype "input"))
      (node (ref "R43") (pin "2") (pinfunction "2_2") (pintype "passive"))
    )
    (net (code "76") (name "Net-(IC15-ROUT1)") (class "Default")
      (node (ref "IC15") (pin "7") (pinfunction "ROUT1_7") (pintype "output"))
      (node (ref "R45") (pin "2") (pinfunction "2_2") (pintype "passive"))
    )
    (net (code "77") (name "Net-(IC15-ROUT2)") (class "Default")
      (node (ref "IC15") (pin "6") (pinfunction "ROUT2_6") (pintype "output"))
      (node (ref "R47") (pin "2") (pinfunction "2_2") (pintype "passive"))
    )
    (net (code "78") (name "Net-(IC21-ROUT1)") (class "Default")
      (node (ref "IC21") (pin "7") (pinfunction "ROUT1_7") (pintype "output"))
      (node (ref "R117") (pin "2") (pinfunction "2_2") (pintype "passive"))
    )
    (net (code "79") (name "Net-(IC21-ROUT2)") (class "Default")
      (node (ref "IC21") (pin "6") (pinfunction "ROUT2_6") (pintype "output"))
      (node (ref "R119") (pin "2") (pinfunction "2_2") (pintype "passive"))
    )
    (net (code "80") (name "Net-(T17-D)") (class "Default")
      (node (ref "R72") (pin "1") (pinfunction "1_1") (pintype "passive"))
      (node (ref "T17") (pin "3") (pinfunction "D_3") (pintype "passive"))
    )
    (net (code "81") (name "P3V3") (class "Default")
      (node (ref "C10") (pin "2") (pinfunction "2_2") (pintype "passive"))
      (node (ref "C116") (pin "2") (pinfunction "2_2") (pintype "passive"))
      (node (ref "C32") (pin "2") (pinfunction "2_2") (pintype "passive"))
      (node (ref "C62") (pin "2") (pinfunction "2_2") (pintype "passive"))
      (node (ref "C63") (pin "2") (pinfunction "2_2") (pintype "passive"))
      (node (ref "C64") (pin "2") (pinfunction "2_2") (pintype "passive"))
      (node (ref "IC13") (pin "8") (pinfunction "VCC_8") (pintype "power_in"))
      (node (ref "IC14") (pin "1") (pinfunction "VCC_1") (pintype "power_in"))
      (node (ref "IC15") (pin "8") (pinfunction "VCC_8") (pintype "power_in"))
      (node (ref "IC21") (pin "8") (pinfunction "VCC_8") (pintype "power_in"))
      (node (ref "IC4") (pin "1") (pinfunction "VCC_1") (pintype "power_in"))
      (node (ref "IC6") (pin "8") (pinfunction "VCC_8") (pintype "power_in"))
    )
    (net (code "82") (name "P3V3_MP") (class "Default")
      (node (ref "C100") (pin "2") (pinfunction "2_2") (pintype "passive"))
      (node (ref "C103") (pin "2") (pinfunction "2_2") (pintype "passive"))
      (node (ref "C65") (pin "2") (pinfunction "2_2") (pintype "passive"))
      (node (ref "C75") (pin "2") (pinfunction "2_2") (pintype "passive"))
      (node (ref "C76") (pin "2") (pinfunction "2_2") (pintype "passive"))
      (node (ref "IC16") (pin "4") (pinfunction "VCC_4") (pintype "power_in"))
      (node (ref "IC26") (pin "8") (pinfunction "+VS_8") (pintype "power_in"))
      (node (ref "IC27") (pin "7") (pinfunction "A0_7") (pintype "input"))
      (node (ref "IC27") (pin "8") (pinfunction "+VS_8") (pintype "power_in"))
      (node (ref "IC32") (pin "14") (pinfunction "VCC_14") (pintype "power_in"))
      (node (ref "IC43") (pin "8") (pinfunction "VCC_8") (pintype "power_in"))
      (node (ref "J9") (pin "30") (pinfunction "30_30") (pintype "bidirectional"))
      (node (ref "R61") (pin "1") (pinfunction "1_1") (pintype "passive"))
    )
    (net (code "83") (name "P12V0") (class "Default")
      (node (ref "C99") (pin "2") (pinfunction "2_2") (pintype "passive"))
      (node (ref "J9") (pin "28") (pinfunction "28_28") (pintype "bidirectional"))
      (node (ref "J9") (pin "29") (pinfunction "29_29") (pintype "bidirectional"))
      (node (ref "R41") (pin "1") (pinfunction "1_1") (pintype "passive"))
      (node (ref "R48") (pin "1") (pinfunction "1_1") (pintype "passive"))
      (node (ref "R49") (pin "1") (pinfunction "1_1") (pintype "passive"))
      (node (ref "R50") (pin "1") (pinfunction "1_1") (pintype "passive"))
      (node (ref "R51") (pin "2") (pinfunction "2_2") (pintype "passive"))
      (node (ref "T13") (pin "1") (pinfunction "S_1") (pintype "passive"))
      (node (ref "T13") (pin "2") (pinfunction "S_2") (pintype "passive"))
      (node (ref "T13") (pin "3") (pinfunction "S_3") (pintype "passive"))
    )
    (net (code "84") (name "P12V0_DIOT") (class "Default")
      (node (ref "R41") (pin "2") (pinfunction "2_2") (pintype "passive"))
      (node (ref "R48") (pin "2") (pinfunction "2_2") (pintype "passive"))
      (node (ref "R49") (pin "2") (pinfunction "2_2") (pintype "passive"))
      (node (ref "R50") (pin "2") (pinfunction "2_2") (pintype "passive"))
    )
    (net (code "85") (name "P12V0_SW") (class "Default")
      (node (ref "T13") (pin "5") (pinfunction "D_5") (pintype "passive"))
      (node (ref "T13") (pin "6") (pinfunction "D_6") (pintype "passive"))
      (node (ref "T13") (pin "7") (pinfunction "D_7") (pintype "passive"))
      (node (ref "T13") (pin "8") (pinfunction "D_8") (pintype "passive"))
    )
    (net (code "86") (name "unconnected-(D5A-C-Pad1)") (class "Default")
      (node (ref "D5") (pin "1") (pinfunction "C_1") (pintype "passive+no_connect"))
    )
    (net (code "87") (name "unconnected-(D5B-C-Pad3)") (class "Default")
      (node (ref "D5") (pin "3") (pinfunction "C_3") (pintype "passive+no_connect"))
    )
    (net (code "88") (name "unconnected-(D5D-C-Pad5)") (class "Default")
      (node (ref "D5") (pin "5") (pinfunction "C_5") (pintype "passive+no_connect"))
    )
    (net (code "89") (name "unconnected-(IC4-DIN2RIN--Pad3)") (class "Default")
      (node (ref "IC4") (pin "3") (pinfunction "DIN2RIN-_3") (pintype "input+no_connect"))
    )
    (net (code "90") (name "unconnected-(IC4-DOUT+-Pad6)") (class "Default")
      (node (ref "IC4") (pin "6") (pinfunction "DOUT+_6") (pintype "output+no_connect"))
    )
    (net (code "91") (name "unconnected-(IC4-DOUT--Pad5)") (class "Default")
      (node (ref "IC4") (pin "5") (pinfunction "DOUT-_5") (pintype "output+no_connect"))
    )
    (net (code "92") (name "unconnected-(IC13-RIN2+-Pad3)") (class "Default")
      (node (ref "IC13") (pin "3") (pinfunction "RIN2+_3") (pintype "input+no_connect"))
    )
    (net (code "93") (name "unconnected-(IC13-RIN2--Pad4)") (class "Default")
      (node (ref "IC13") (pin "4") (pinfunction "RIN2-_4") (pintype "input+no_connect"))
    )
    (net (code "94") (name "unconnected-(IC13-ROUT2-Pad6)") (class "Default")
      (node (ref "IC13") (pin "6") (pinfunction "ROUT2_6") (pintype "output+no_connect"))
    )
    (net (code "95") (name "unconnected-(IC16-NC-Pad5)") (class "Default")
      (node (ref "IC16") (pin "5") (pinfunction "NC_5") (pintype "passive+no_connect"))
    )
    (net (code "96") (name "unconnected-(IC43-NC-Pad7)") (class "Default")
      (node (ref "IC43") (pin "7") (pinfunction "NC_7") (pintype "passive+no_connect"))
    )
  )
)
